# I2C-sensors.net
KiCad netlist of a schematic drawn in Altium Designer
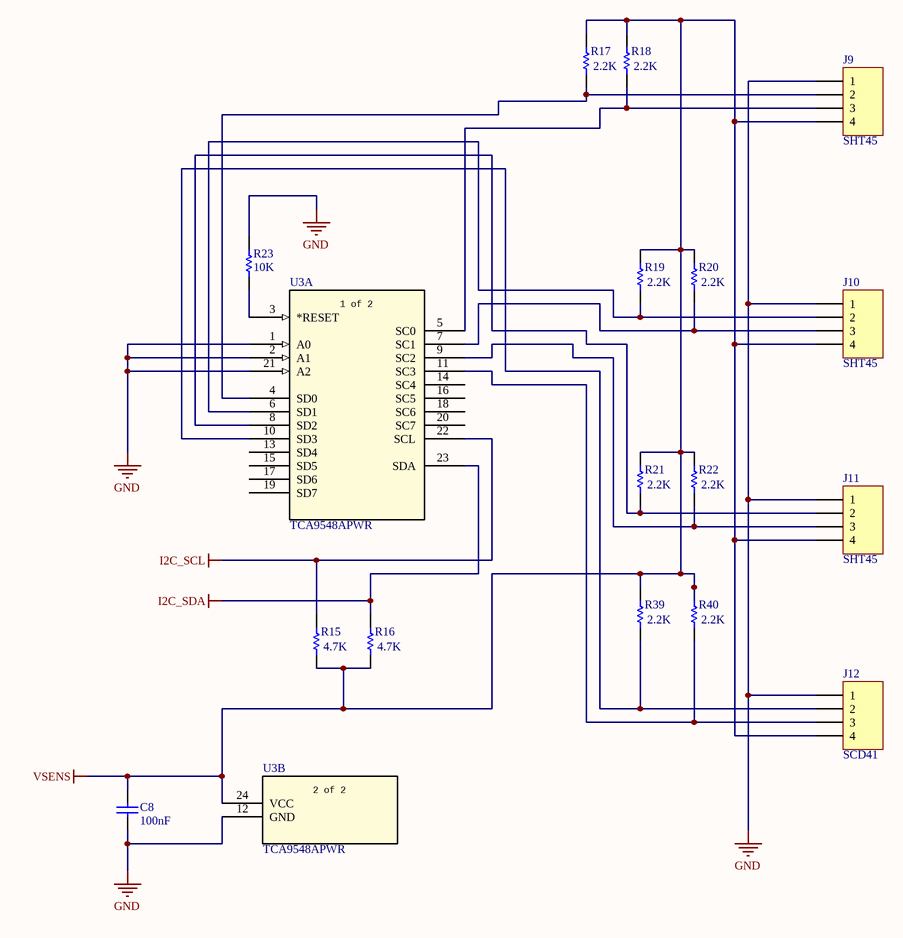
[diagram p0: I2C-sensors.SchDoc]

(export (version "E")
  (design (tool "Eeschema 10.0.6"))
  (components
    (comp (ref "C8")
      (value "100nF")
      (footprint "WaterTempNode_FE:CHIP0805-M")
      (description "Capacitor")
      (fields (field (name "PUBLISHER") "Altium Limited"))
      (libsource (lib "Miscellaneous Devices") (part "Cap"))
    )
    (comp (ref "J9")
      (value "SHT45")
      (footprint "WaterTempNode_FE:PHX-MC15-4-G-35")
      (description "Header, 4-Pin")
      (fields (field (name "PUBLISHER") "Altium Limited"))
      (libsource (lib "Miscellaneous Connectors") (part "Header 4"))
    )
    (comp (ref "J10")
      (value "SHT45")
      (footprint "WaterTempNode_FE:PHX-MC15-4-G-35")
      (description "Header, 4-Pin")
      (fields (field (name "PUBLISHER") "Altium Limited"))
      (libsource (lib "Miscellaneous Connectors") (part "Header 4"))
    )
    (comp (ref "J11")
      (value "SHT45")
      (footprint "WaterTempNode_FE:PHX-MC15-4-G-35")
      (description "Header, 4-Pin")
      (fields (field (name "PUBLISHER") "Altium Limited"))
      (libsource (lib "Miscellaneous Connectors") (part "Header 4"))
    )
    (comp (ref "J12")
      (value "SCD41")
      (footprint "WaterTempNode_FE:PHX-MC15-4-G-35")
      (description "Header, 4-Pin")
      (fields (field (name "PUBLISHER") "Altium Limited"))
      (libsource (lib "Miscellaneous Connectors") (part "Header 4"))
    )
    (comp (ref "R15")
      (value "4.7K")
      (footprint "WaterTempNode_FE:CHIP0805-M")
      (description "Resistor")
      (fields (field (name "Comment") "pullup") (field (name "PUBLISHER") "Altium Limited"))
      (libsource (lib "Miscellaneous Devices") (part "Res1"))
    )
    (comp (ref "R16")
      (value "4.7K")
      (footprint "WaterTempNode_FE:CHIP0805-M")
      (description "Resistor")
      (fields (field (name "Comment") "pullup") (field (name "PUBLISHER") "Altium Limited"))
      (libsource (lib "Miscellaneous Devices") (part "Res1"))
    )
    (comp (ref "R17")
      (value "2.2K")
      (footprint "WaterTempNode_FE:CHIP0805-M")
      (description "Resistor")
      (fields (field (name "Comment") "pullup") (field (name "PUBLISHER") "Altium Limited"))
      (libsource (lib "Miscellaneous Devices") (part "Res1"))
    )
    (comp (ref "R18")
      (value "2.2K")
      (footprint "WaterTempNode_FE:CHIP0805-M")
      (description "Resistor")
      (fields (field (name "Comment") "pullup") (field (name "PUBLISHER") "Altium Limited"))
      (libsource (lib "Miscellaneous Devices") (part "Res1"))
    )
    (comp (ref "R19")
      (value "2.2K")
      (footprint "WaterTempNode_FE:CHIP0805-M")
      (description "Resistor")
      (fields (field (name "Comment") "pullup") (field (name "PUBLISHER") "Altium Limited"))
      (libsource (lib "Miscellaneous Devices") (part "Res1"))
    )
    (comp (ref "R20")
      (value "2.2K")
      (footprint "WaterTempNode_FE:CHIP0805-M")
      (description "Resistor")
      (fields (field (name "Comment") "pullup") (field (name "PUBLISHER") "Altium Limited"))
      (libsource (lib "Miscellaneous Devices") (part "Res1"))
    )
    (comp (ref "R21")
      (value "2.2K")
      (footprint "WaterTempNode_FE:CHIP0805-M")
      (description "Resistor")
      (fields (field (name "Comment") "pullup") (field (name "PUBLISHER") "Altium Limited"))
      (libsource (lib "Miscellaneous Devices") (part "Res1"))
    )
    (comp (ref "R22")
      (value "2.2K")
      (footprint "WaterTempNode_FE:CHIP0805-M")
      (description "Resistor")
      (fields (field (name "Comment") "pullup") (field (name "PUBLISHER") "Altium Limited"))
      (libsource (lib "Miscellaneous Devices") (part "Res1"))
    )
    (comp (ref "R23")
      (value "10K")
      (footprint "WaterTempNode_FE:CHIP0805-M")
      (description "Resistor")
      (fields (field (name "Comment") "220R") (field (name "PUBLISHER") "Altium Limited"))
      (libsource (lib "Miscellaneous Devices") (part "Res1"))
    )
    (comp (ref "R39")
      (value "2.2K")
      (footprint "WaterTempNode_FE:CHIP0805-M")
      (description "Resistor")
      (fields (field (name "Comment") "pullup") (field (name "PUBLISHER") "Altium Limited"))
      (libsource (lib "Miscellaneous Devices") (part "Res1"))
    )
    (comp (ref "R40")
      (value "2.2K")
      (footprint "WaterTempNode_FE:CHIP0805-M")
      (description "Resistor")
      (fields (field (name "Comment") "pullup") (field (name "PUBLISHER") "Altium Limited"))
      (libsource (lib "Miscellaneous Devices") (part "Res1"))
    )
    (comp (ref "U3")
      (value "TCA9548APWR")
      (footprint "PW24_TEX")
      (description "8-channel 1.65- to 5.5-V I2C/SMBus switch with reset & voltage translation 24-TSSOP -40 to 85")
      (fields (field (name "COPYRIGHT") "Copyright (C) 2025 Ultra Librarian. All rights reserved."))
      (libsource (lib "TCA9548APWR") (part "TCA9548APWR"))
    )
  )
  (nets
    (net (code "1") (name "GND") (class "Default")
      (node (ref "C8") (pin "2") (pinfunction "2_2") (pintype "passive"))
      (node (ref "J10") (pin "1") (pinfunction "1_1") (pintype "passive"))
      (node (ref "J11") (pin "1") (pinfunction "1_1") (pintype "passive"))
      (node (ref "J12") (pin "1") (pinfunction "1_1") (pintype "passive"))
      (node (ref "J9") (pin "1") (pinfunction "1_1") (pintype "passive"))
      (node (ref "R23") (pin "1") (pinfunction "1_1") (pintype "passive"))
      (node (ref "U3") (pin "1") (pinfunction "A0_1") (pintype "input"))
      (node (ref "U3") (pin "12") (pinfunction "GND_12") (pintype "power_in"))
      (node (ref "U3") (pin "2") (pinfunction "A1_2") (pintype "input"))
      (node (ref "U3") (pin "21") (pinfunction "A2_21") (pintype "input"))
    )
    (net (code "2") (name "I2C_SCL") (class "Default")
      (node (ref "R15") (pin "2") (pinfunction "2_2") (pintype "passive"))
      (node (ref "U3") (pin "22") (pinfunction "SCL_22") (pintype "passive"))
    )
    (net (code "3") (name "I2C_SDA") (class "Default")
      (node (ref "R16") (pin "2") (pinfunction "2_2") (pintype "passive"))
      (node (ref "U3") (pin "23") (pinfunction "SDA_23") (pintype "passive"))
    )
    (net (code "4") (name "Net-(U3A-*RESET)") (class "Default")
      (node (ref "R23") (pin "2") (pinfunction "2_2") (pintype "passive"))
      (node (ref "U3") (pin "3") (pinfunction "*RESET_3") (pintype "input"))
    )
    (net (code "5") (name "Net-(U3A-SC0)") (class "Default")
      (node (ref "J9") (pin "3") (pinfunction "3_3") (pintype "passive"))
      (node (ref "R18") (pin "1") (pinfunction "1_1") (pintype "passive"))
      (node (ref "U3") (pin "5") (pinfunction "SC0_5") (pintype "passive"))
    )
    (net (code "6") (name "Net-(U3A-SC1)") (class "Default")
      (node (ref "J10") (pin "3") (pinfunction "3_3") (pintype "passive"))
      (node (ref "R20") (pin "1") (pinfunction "1_1") (pintype "passive"))
      (node (ref "U3") (pin "7") (pinfunction "SC1_7") (pintype "passive"))
    )
    (net (code "7") (name "Net-(U3A-SC2)") (class "Default")
      (node (ref "J11") (pin "3") (pinfunction "3_3") (pintype "passive"))
      (node (ref "R22") (pin "1") (pinfunction "1_1") (pintype "passive"))
      (node (ref "U3") (pin "9") (pinfunction "SC2_9") (pintype "passive"))
    )
    (net (code "8") (name "Net-(U3A-SC3)") (class "Default")
      (node (ref "J12") (pin "3") (pinfunction "3_3") (pintype "passive"))
      (node (ref "R40") (pin "1") (pinfunction "1_1") (pintype "passive"))
      (node (ref "U3") (pin "11") (pinfunction "SC3_11") (pintype "passive"))
    )
    (net (code "9") (name "Net-(U3A-SD0)") (class "Default")
      (node (ref "J9") (pin "2") (pinfunction "2_2") (pintype "passive"))
      (node (ref "R17") (pin "1") (pinfunction "1_1") (pintype "passive"))
      (node (ref "U3") (pin "4") (pinfunction "SD0_4") (pintype "passive"))
    )
    (net (code "10") (name "Net-(U3A-SD1)") (class "Default")
      (node (ref "J10") (pin "2") (pinfunction "2_2") (pintype "passive"))
      (node (ref "R19") (pin "1") (pinfunction "1_1") (pintype "passive"))
      (node (ref "U3") (pin "6") (pinfunction "SD1_6") (pintype "passive"))
    )
    (net (code "11") (name "Net-(U3A-SD2)") (class "Default")
      (node (ref "J11") (pin "2") (pinfunction "2_2") (pintype "passive"))
      (node (ref "R21") (pin "1") (pinfunction "1_1") (pintype "passive"))
      (node (ref "U3") (pin "8") (pinfunction "SD2_8") (pintype "passive"))
    )
    (net (code "12") (name "Net-(U3A-SD3)") (class "Default")
      (node (ref "J12") (pin "2") (pinfunction "2_2") (pintype "passive"))
      (node (ref "R39") (pin "1") (pinfunction "1_1") (pintype "passive"))
      (node (ref "U3") (pin "10") (pinfunction "SD3_10") (pintype "passive"))
    )
    (net (code "13") (name "VSENS") (class "Default")
      (node (ref "C8") (pin "1") (pinfunction "1_1") (pintype "passive"))
      (node (ref "J10") (pin "4") (pinfunction "4_4") (pintype "passive"))
      (node (ref "J11") (pin "4") (pinfunction "4_4") (pintype "passive"))
      (node (ref "J12") (pin "4") (pinfunction "4_4") (pintype "passive"))
      (node (ref "J9") (pin "4") (pinfunction "4_4") (pintype "passive"))
      (node (ref "R15") (pin "1") (pinfunction "1_1") (pintype "passive"))
      (node (ref "R16") (pin "1") (pinfunction "1_1") (pintype "passive"))
      (node (ref "R17") (pin "2") (pinfunction "2_2") (pintype "passive"))
      (node (ref "R18") (pin "2") (pinfunction "2_2") (pintype "passive"))
      (node (ref "R19") (pin "2") (pinfunction "2_2") (pintype "passive"))
      (node (ref "R20") (pin "2") (pinfunction "2_2") (pintype "passive"))
      (node (ref "R21") (pin "2") (pinfunction "2_2") (pintype "passive"))
      (node (ref "R22") (pin "2") (pinfunction "2_2") (pintype "passive"))
      (node (ref "R39") (pin "2") (pinfunction "2_2") (pintype "passive"))
      (node (ref "R40") (pin "2") (pinfunction "2_2") (pintype "passive"))
      (node (ref "U3") (pin "24") (pinfunction "VCC_24") (pintype "power_in"))
    )
    (net (code "14") (name "unconnected-(U3A-SC4-Pad14)") (class "Default")
      (node (ref "U3") (pin "14") (pinfunction "SC4_14") (pintype "passive"))
    )
    (net (code "15") (name "unconnected-(U3A-SC5-Pad16)") (class "Default")
      (node (ref "U3") (pin "16") (pinfunction "SC5_16") (pintype "passive"))
    )
    (net (code "16") (name "unconnected-(U3A-SC6-Pad18)") (class "Default")
      (node (ref "U3") (pin "18") (pinfunction "SC6_18") (pintype "passive"))
    )
    (net (code "17") (name "unconnected-(U3A-SC7-Pad20)") (class "Default")
      (node (ref "U3") (pin "20") (pinfunction "SC7_20") (pintype "passive"))
    )
    (net (code "18") (name "unconnected-(U3A-SD4-Pad13)") (class "Default")
      (node (ref "U3") (pin "13") (pinfunction "SD4_13") (pintype "passive"))
    )
    (net (code "19") (name "unconnected-(U3A-SD5-Pad15)") (class "Default")
      (node (ref "U3") (pin "15") (pinfunction "SD5_15") (pintype "passive"))
    )
    (net (code "20") (name "unconnected-(U3A-SD6-Pad17)") (class "Default")
      (node (ref "U3") (pin "17") (pinfunction "SD6_17") (pintype "passive"))
    )
    (net (code "21") (name "unconnected-(U3A-SD7-Pad19)") (class "Default")
      (node (ref "U3") (pin "19") (pinfunction "SD7_19") (pintype "passive"))
    )
  )
)
